# mcu.net
KiCad netlist of a schematic drawn in Altium Designer
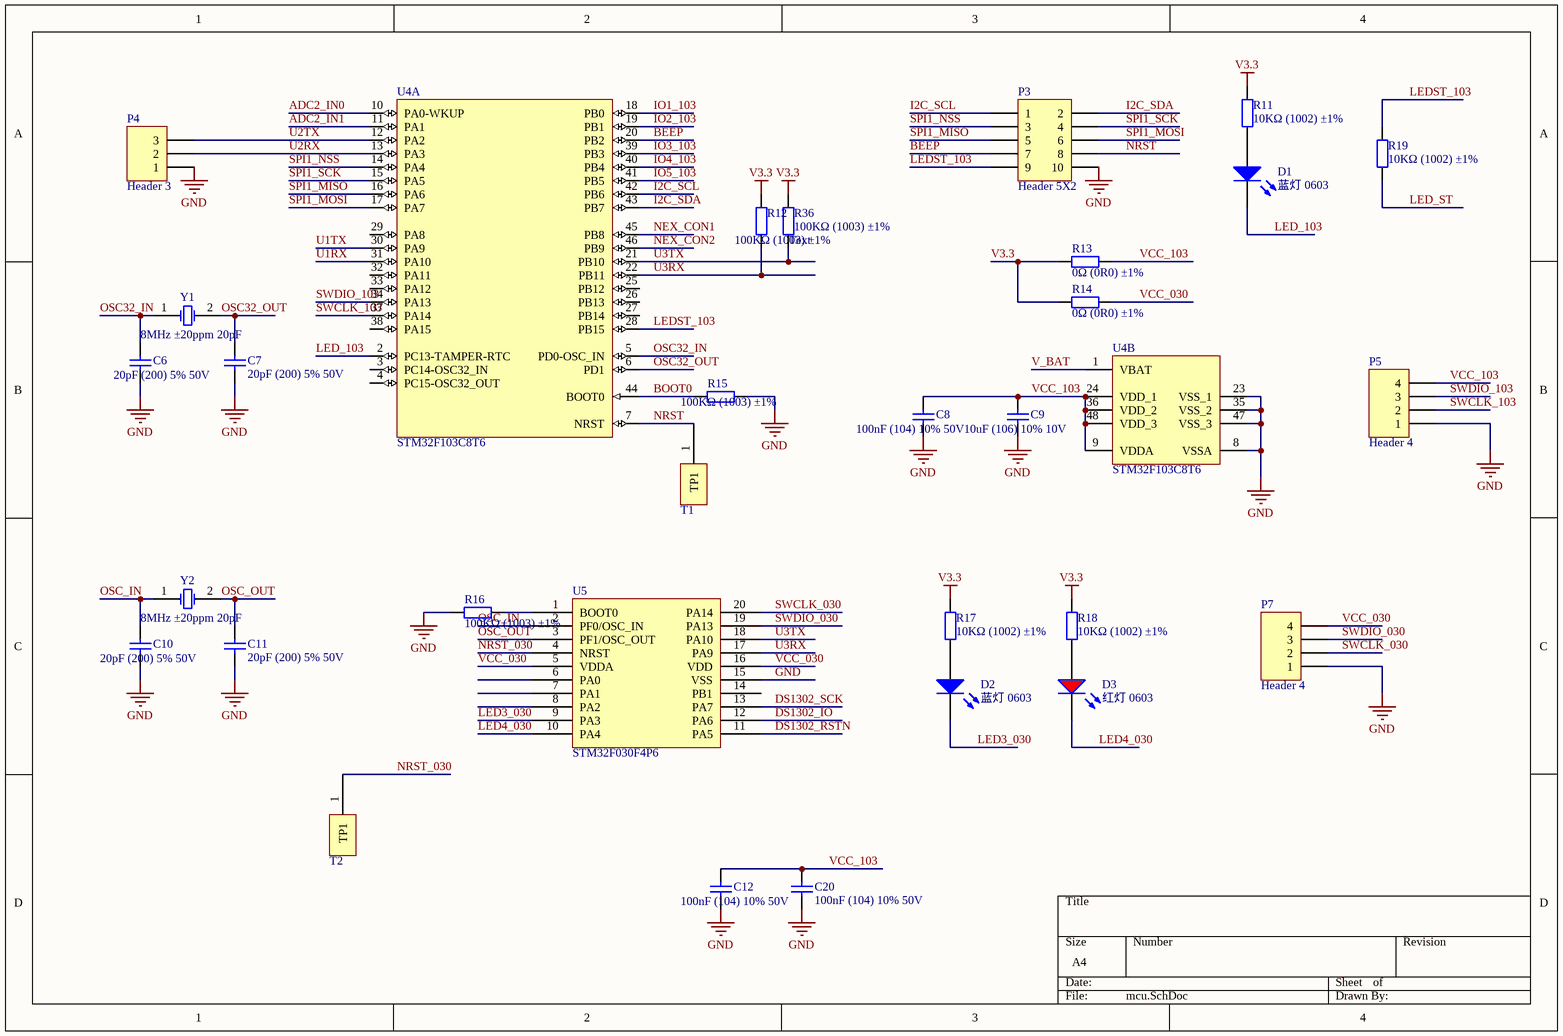
[diagram p0: mcu.SchDoc]

(export (version "E")
  (design (tool "Eeschema 10.0.6"))
  (components
    (comp (ref "C6")
      (value "20pF (200) 5% 50V")
      (footprint "0603_C")
      (description "贴片电容")
      (libsource (lib "Miscellaneous Devices LC") (part "0603 20pF (200) 5% 50V"))
    )
    (comp (ref "C7")
      (value "20pF (200) 5% 50V")
      (footprint "0603_C")
      (description "贴片电容")
      (libsource (lib "Miscellaneous Devices LC") (part "0603 20pF (200) 5% 50V"))
    )
    (comp (ref "C8")
      (value "100nF (104) 10% 50V")
      (footprint "0603_C")
      (description "贴片电容")
      (libsource (lib "Miscellaneous Devices LC") (part "0603 100nF (104) 10% 50V"))
    )
    (comp (ref "C9")
      (value "10uF (106) 10% 10V")
      (footprint "0603_C")
      (description "贴片电容")
      (libsource (lib "Miscellaneous Devices LC") (part "0603 10uF (106) 10% 10V"))
    )
    (comp (ref "C10")
      (value "20pF (200) 5% 50V")
      (footprint "0603_C")
      (description "贴片电容")
      (libsource (lib "Miscellaneous Devices LC") (part "0603 20pF (200) 5% 50V"))
    )
    (comp (ref "C11")
      (value "20pF (200) 5% 50V")
      (footprint "0603_C")
      (description "贴片电容")
      (libsource (lib "Miscellaneous Devices LC") (part "0603 20pF (200) 5% 50V"))
    )
    (comp (ref "C12")
      (value "100nF (104) 10% 50V")
      (footprint "1206_C")
      (description "贴片电容")
      (libsource (lib "Miscellaneous Devices LC") (part "1206 100nF (104) 10% 50V"))
    )
    (comp (ref "C20")
      (value "100nF (104) 10% 50V")
      (footprint "1206_C")
      (description "贴片电容")
      (libsource (lib "Miscellaneous Devices LC") (part "1206 100nF (104) 10% 50V"))
    )
    (comp (ref "D1")
      (value "蓝灯 0603")
      (footprint "0603_LED_S1")
      (description "发光二极管")
      (libsource (lib "Miscellaneous Devices LC") (part "0603 蓝灯"))
    )
    (comp (ref "D2")
      (value "蓝灯 0603")
      (footprint "0603_LED_S1")
      (description "发光二极管")
      (libsource (lib "Miscellaneous Devices LC") (part "0603 蓝灯"))
    )
    (comp (ref "D3")
      (value "红灯 0603")
      (footprint "0603_LED_S1")
      (description "发光二极管")
      (libsource (lib "Miscellaneous Devices LC") (part "0603 红灯"))
    )
    (comp (ref "P3")
      (value "Header 5X2")
      (footprint "HDR2X5")
      (description "Header, 5-Pin, Dual row")
      (fields (field (name "PUBLISHER") "Altium Limited"))
      (libsource (lib "Miscellaneous Connectors") (part "Header 5X2"))
    )
    (comp (ref "P4")
      (value "Header 3")
      (footprint "HDR1X3")
      (description "Header, 3-Pin")
      (fields (field (name "PUBLISHER") "Altium Limited"))
      (libsource (lib "Miscellaneous Connectors") (part "Header 3"))
    )
    (comp (ref "P5")
      (value "Header 4")
      (footprint "HDR1X4")
      (description "Header, 4-Pin")
      (fields (field (name "PUBLISHER") "Altium Limited"))
      (libsource (lib "Miscellaneous Connectors") (part "Header 4"))
    )
    (comp (ref "P7")
      (value "Header 4")
      (footprint "HDR1X4")
      (description "Header, 4-Pin")
      (fields (field (name "PUBLISHER") "Altium Limited"))
      (libsource (lib "Miscellaneous Connectors") (part "Header 4"))
    )
    (comp (ref "R11")
      (value "10KΩ (1002) ±1%")
      (footprint "0603_R")
      (description "贴片电阻")
      (libsource (lib "Miscellaneous Devices LC") (part "0603 10KΩ (1002) 1%"))
    )
    (comp (ref "R12")
      (value "100KΩ (1003) ±1%")
      (footprint "0603_R")
      (description "贴片电阻")
      (libsource (lib "Miscellaneous Devices LC") (part "0603 100KΩ (1003) 1%"))
    )
    (comp (ref "R13")
      (value "0Ω (0R0) ±1%")
      (footprint "1206_R")
      (description "贴片电阻")
      (libsource (lib "Miscellaneous Devices LC") (part "1206 0Ω (0R0) 1%"))
    )
    (comp (ref "R14")
      (value "0Ω (0R0) ±1%")
      (footprint "1206_R")
      (description "贴片电阻")
      (libsource (lib "Miscellaneous Devices LC") (part "1206 0Ω (0R0) 1%"))
    )
    (comp (ref "R15")
      (value "100KΩ (1003) ±1%")
      (footprint "0603_R")
      (description "贴片电阻")
      (libsource (lib "") (part "0603 100KΩ (1003) 1%_1"))
    )
    (comp (ref "R16")
      (value "100KΩ (1003) ±1%")
      (footprint "0603_R")
      (description "贴片电阻")
      (libsource (lib "") (part "0603 100KΩ (1003) 1%_1"))
    )
    (comp (ref "R17")
      (value "10KΩ (1002) ±1%")
      (footprint "0603_R")
      (description "贴片电阻")
      (libsource (lib "Miscellaneous Devices LC") (part "0603 10KΩ (1002) 1%"))
    )
    (comp (ref "R18")
      (value "10KΩ (1002) ±1%")
      (footprint "0603_R")
      (description "贴片电阻")
      (libsource (lib "Miscellaneous Devices LC") (part "0603 10KΩ (1002) 1%"))
    )
    (comp (ref "R19")
      (value "10KΩ (1002) ±1%")
      (footprint "0603_R")
      (description "贴片电阻")
      (libsource (lib "Miscellaneous Devices LC") (part "0603 10KΩ (1002) 1%"))
    )
    (comp (ref "R36")
      (value "100KΩ (1003) ±1%")
      (footprint "0603_R")
      (description "贴片电阻")
      (libsource (lib "Miscellaneous Devices LC") (part "0603 100KΩ (1003) 1%"))
    )
    (comp (ref "T1") (value "TP1") (footprint "TP1") (libsource (lib "CHK-I") (part "TP1")))
    (comp (ref "T2") (value "TP1") (footprint "TP1") (libsource (lib "CHK-I") (part "TP1")))
    (comp (ref "U4")
      (value "STM32F103C8T6")
      (footprint "LQFP-48_7x7x05P")
      (description "ARM")
      (libsource (lib "Miscellaneous Devices LC") (part "STM32F103C8T6"))
    )
    (comp (ref "U5")
      (value "STM32F030F4P6")
      (footprint "TSSOP-20")
      (description "ARM")
      (libsource (lib "Miscellaneous Devices LC") (part "STM32F030F4P6"))
    )
    (comp (ref "Y1")
      (value "8MHz ±20ppm 20pF")
      (footprint "SMD-5032_2P")
      (description "贴片晶振")
      (libsource (lib "Miscellaneous Devices LC") (part "SMD-5032_2P 8MHz 20ppm 20pF"))
    )
    (comp (ref "Y2")
      (value "8MHz ±20ppm 20pF")
      (footprint "SMD-5032_2P")
      (description "贴片晶振")
      (libsource (lib "Miscellaneous Devices LC") (part "SMD-5032_2P 8MHz 20ppm 20pF"))
    )
  )
  (nets
    (net (code "1") (name "/ADC2_IN0") (class "Default")
      (node (ref "U4") (pin "10") (pinfunction "PA0-WKUP_10") (pintype "bidirectional"))
    )
    (net (code "2") (name "/ADC2_IN1") (class "Default")
      (node (ref "U4") (pin "11") (pinfunction "PA1_11") (pintype "bidirectional"))
    )
    (net (code "3") (name "/BEEP") (class "Default")
      (node (ref "P3") (pin "7") (pinfunction "7_7") (pintype "passive"))
      (node (ref "U4") (pin "20") (pinfunction "PB2_20") (pintype "bidirectional"))
    )
    (net (code "4") (name "/BOOT0") (class "Default")
      (node (ref "R15") (pin "1") (pinfunction "1_1") (pintype "passive"))
      (node (ref "U4") (pin "44") (pinfunction "BOOT0_44") (pintype "input"))
    )
    (net (code "5") (name "/DS1302_IO") (class "Default")
      (node (ref "U5") (pin "12") (pinfunction "PA6_12") (pintype "passive"))
    )
    (net (code "6") (name "/DS1302_RSTN") (class "Default")
      (node (ref "U5") (pin "11") (pinfunction "PA5_11") (pintype "passive"))
    )
    (net (code "7") (name "/DS1302_SCK") (class "Default")
      (node (ref "U5") (pin "13") (pinfunction "PA7_13") (pintype "passive"))
    )
    (net (code "8") (name "/I2C_SCL") (class "Default")
      (node (ref "P3") (pin "1") (pinfunction "1_1") (pintype "passive"))
      (node (ref "U4") (pin "42") (pinfunction "PB6_42") (pintype "bidirectional"))
    )
    (net (code "9") (name "/I2C_SDA") (class "Default")
      (node (ref "P3") (pin "2") (pinfunction "2_2") (pintype "passive"))
      (node (ref "U4") (pin "43") (pinfunction "PB7_43") (pintype "bidirectional"))
    )
    (net (code "10") (name "/IO1_103") (class "Default")
      (node (ref "U4") (pin "18") (pinfunction "PB0_18") (pintype "bidirectional"))
    )
    (net (code "11") (name "/IO2_103") (class "Default")
      (node (ref "U4") (pin "19") (pinfunction "PB1_19") (pintype "bidirectional"))
    )
    (net (code "12") (name "/IO3_103") (class "Default")
      (node (ref "U4") (pin "39") (pinfunction "PB3_39") (pintype "bidirectional"))
    )
    (net (code "13") (name "/IO4_103") (class "Default")
      (node (ref "U4") (pin "40") (pinfunction "PB4_40") (pintype "bidirectional"))
    )
    (net (code "14") (name "/IO5_103") (class "Default")
      (node (ref "U4") (pin "41") (pinfunction "PB5_41") (pintype "bidirectional"))
    )
    (net (code "15") (name "/LED3_030") (class "Default")
      (node (ref "D2") (pin "K") (pinfunction "K_K") (pintype "passive"))
      (node (ref "U5") (pin "9") (pinfunction "PA3_9") (pintype "passive"))
    )
    (net (code "16") (name "/LED4_030") (class "Default")
      (node (ref "D3") (pin "K") (pinfunction "K_K") (pintype "passive"))
      (node (ref "U5") (pin "10") (pinfunction "PA4_10") (pintype "passive"))
    )
    (net (code "17") (name "/LEDST_103") (class "Default")
      (node (ref "P3") (pin "9") (pinfunction "9_9") (pintype "passive"))
      (node (ref "R19") (pin "2") (pinfunction "2_2") (pintype "passive"))
      (node (ref "U4") (pin "28") (pinfunction "PB15_28") (pintype "bidirectional"))
    )
    (net (code "18") (name "/LED_103") (class "Default")
      (node (ref "D1") (pin "K") (pinfunction "K_K") (pintype "passive"))
      (node (ref "U4") (pin "2") (pinfunction "PC13-TAMPER-RTC_2") (pintype "bidirectional"))
    )
    (net (code "19") (name "/LED_ST") (class "Default")
      (node (ref "R19") (pin "1") (pinfunction "1_1") (pintype "passive"))
    )
    (net (code "20") (name "/NEX_CON1") (class "Default")
      (node (ref "U4") (pin "45") (pinfunction "PB8_45") (pintype "bidirectional"))
    )
    (net (code "21") (name "/NEX_CON2") (class "Default")
      (node (ref "U4") (pin "46") (pinfunction "PB9_46") (pintype "bidirectional"))
    )
    (net (code "22") (name "/NRST") (class "Default")
      (node (ref "P3") (pin "8") (pinfunction "8_8") (pintype "passive"))
      (node (ref "T1") (pin "1") (pinfunction "TP1_1") (pintype "passive"))
      (node (ref "U4") (pin "7") (pinfunction "NRST_7") (pintype "bidirectional"))
    )
    (net (code "23") (name "/NRST_030") (class "Default")
      (node (ref "T2") (pin "1") (pinfunction "TP1_1") (pintype "passive"))
      (node (ref "U5") (pin "4") (pinfunction "NRST_4") (pintype "passive"))
    )
    (net (code "24") (name "/OSC32_IN") (class "Default")
      (node (ref "C6") (pin "2") (pinfunction "2_2") (pintype "passive"))
      (node (ref "U4") (pin "5") (pinfunction "PD0-OSC_IN_5") (pintype "bidirectional"))
      (node (ref "Y1") (pin "1") (pinfunction "OSC1_1") (pintype "passive"))
    )
    (net (code "25") (name "/OSC32_OUT") (class "Default")
      (node (ref "C7") (pin "2") (pinfunction "2_2") (pintype "passive"))
      (node (ref "U4") (pin "6") (pinfunction "PD1_6") (pintype "bidirectional"))
      (node (ref "Y1") (pin "2") (pinfunction "OSC2_2") (pintype "passive"))
    )
    (net (code "26") (name "/OSC_IN") (class "Default")
      (node (ref "C10") (pin "2") (pinfunction "2_2") (pintype "passive"))
      (node (ref "U5") (pin "2") (pinfunction "PF0/OSC_IN_2") (pintype "passive"))
      (node (ref "Y2") (pin "1") (pinfunction "OSC1_1") (pintype "passive"))
    )
    (net (code "27") (name "/OSC_OUT") (class "Default")
      (node (ref "C11") (pin "2") (pinfunction "2_2") (pintype "passive"))
      (node (ref "U5") (pin "3") (pinfunction "PF1/OSC_OUT_3") (pintype "passive"))
      (node (ref "Y2") (pin "2") (pinfunction "OSC2_2") (pintype "passive"))
    )
    (net (code "28") (name "/SPI1_MISO") (class "Default")
      (node (ref "P3") (pin "5") (pinfunction "5_5") (pintype "passive"))
      (node (ref "U4") (pin "16") (pinfunction "PA6_16") (pintype "bidirectional"))
    )
    (net (code "29") (name "/SPI1_MOSI") (class "Default")
      (node (ref "P3") (pin "6") (pinfunction "6_6") (pintype "passive"))
      (node (ref "U4") (pin "17") (pinfunction "PA7_17") (pintype "bidirectional"))
    )
    (net (code "30") (name "/SPI1_NSS") (class "Default")
      (node (ref "P3") (pin "3") (pinfunction "3_3") (pintype "passive"))
      (node (ref "U4") (pin "14") (pinfunction "PA4_14") (pintype "bidirectional"))
    )
    (net (code "31") (name "/SPI1_SCK") (class "Default")
      (node (ref "P3") (pin "4") (pinfunction "4_4") (pintype "passive"))
      (node (ref "U4") (pin "15") (pinfunction "PA5_15") (pintype "bidirectional"))
    )
    (net (code "32") (name "/SWCLK_030") (class "Default")
      (node (ref "P7") (pin "2") (pinfunction "2_2") (pintype "passive"))
      (node (ref "U5") (pin "20") (pinfunction "PA14_20") (pintype "passive"))
    )
    (net (code "33") (name "/SWCLK_103") (class "Default")
      (node (ref "P5") (pin "2") (pinfunction "2_2") (pintype "passive"))
      (node (ref "U4") (pin "37") (pinfunction "PA14_37") (pintype "bidirectional"))
    )
    (net (code "34") (name "/SWDIO_030") (class "Default")
      (node (ref "P7") (pin "3") (pinfunction "3_3") (pintype "passive"))
      (node (ref "U5") (pin "19") (pinfunction "PA13_19") (pintype "passive"))
    )
    (net (code "35") (name "/SWDIO_103") (class "Default")
      (node (ref "P5") (pin "3") (pinfunction "3_3") (pintype "passive"))
      (node (ref "U4") (pin "34") (pinfunction "PA13_34") (pintype "bidirectional"))
    )
    (net (code "36") (name "/U1RX") (class "Default")
      (node (ref "U4") (pin "31") (pinfunction "PA10_31") (pintype "bidirectional"))
    )
    (net (code "37") (name "/U1TX") (class "Default")
      (node (ref "U4") (pin "30") (pinfunction "PA9_30") (pintype "bidirectional"))
    )
    (net (code "38") (name "/U2RX") (class "Default")
      (node (ref "P4") (pin "2") (pinfunction "2_2") (pintype "passive"))
      (node (ref "U4") (pin "13") (pinfunction "PA3_13") (pintype "bidirectional"))
    )
    (net (code "39") (name "/U2TX") (class "Default")
      (node (ref "P4") (pin "3") (pinfunction "3_3") (pintype "passive"))
      (node (ref "U4") (pin "12") (pinfunction "PA2_12") (pintype "bidirectional"))
    )
    (net (code "40") (name "/U3RX") (class "Default")
      (node (ref "R12") (pin "1") (pinfunction "1_1") (pintype "passive"))
      (node (ref "U4") (pin "22") (pinfunction "PB11_22") (pintype "bidirectional"))
      (node (ref "U5") (pin "17") (pinfunction "PA9_17") (pintype "passive"))
    )
    (net (code "41") (name "/U3TX") (class "Default")
      (node (ref "R36") (pin "1") (pinfunction "1_1") (pintype "passive"))
      (node (ref "U4") (pin "21") (pinfunction "PB10_21") (pintype "bidirectional"))
      (node (ref "U5") (pin "18") (pinfunction "PA10_18") (pintype "passive"))
    )
    (net (code "42") (name "/VCC_030") (class "Default")
      (node (ref "P7") (pin "4") (pinfunction "4_4") (pintype "passive"))
      (node (ref "R14") (pin "2") (pinfunction "2_2") (pintype "passive"))
      (node (ref "U5") (pin "16") (pinfunction "VDD_16") (pintype "passive"))
      (node (ref "U5") (pin "5") (pinfunction "VDDA_5") (pintype "passive"))
    )
    (net (code "43") (name "/VCC_103") (class "Default")
      (node (ref "C12") (pin "2") (pinfunction "2_2") (pintype "passive"))
      (node (ref "C20") (pin "2") (pinfunction "2_2") (pintype "passive"))
      (node (ref "C8") (pin "2") (pinfunction "2_2") (pintype "passive"))
      (node (ref "C9") (pin "1") (pinfunction "1_1") (pintype "passive"))
      (node (ref "P5") (pin "4") (pinfunction "4_4") (pintype "passive"))
      (node (ref "R13") (pin "2") (pinfunction "2_2") (pintype "passive"))
      (node (ref "U4") (pin "24") (pinfunction "VDD_1_24") (pintype "power_in"))
      (node (ref "U4") (pin "36") (pinfunction "VDD_2_36") (pintype "power_in"))
      (node (ref "U4") (pin "48") (pinfunction "VDD_3_48") (pintype "power_in"))
      (node (ref "U4") (pin "9") (pinfunction "VDDA_9") (pintype "power_in"))
    )
    (net (code "44") (name "/V_BAT") (class "Default")
      (node (ref "U4") (pin "1") (pinfunction "VBAT_1") (pintype "power_in"))
    )
    (net (code "45") (name "GND") (class "Default")
      (node (ref "C10") (pin "1") (pinfunction "1_1") (pintype "passive"))
      (node (ref "C11") (pin "1") (pinfunction "1_1") (pintype "passive"))
      (node (ref "C12") (pin "1") (pinfunction "1_1") (pintype "passive"))
      (node (ref "C20") (pin "1") (pinfunction "1_1") (pintype "passive"))
      (node (ref "C6") (pin "1") (pinfunction "1_1") (pintype "passive"))
      (node (ref "C7") (pin "1") (pinfunction "1_1") (pintype "passive"))
      (node (ref "C8") (pin "1") (pinfunction "1_1") (pintype "passive"))
      (node (ref "C9") (pin "2") (pinfunction "2_2") (pintype "passive"))
      (node (ref "P3") (pin "10") (pinfunction "10_10") (pintype "passive"))
      (node (ref "P4") (pin "1") (pinfunction "1_1") (pintype "passive"))
      (node (ref "P5") (pin "1") (pinfunction "1_1") (pintype "passive"))
      (node (ref "P7") (pin "1") (pinfunction "1_1") (pintype "passive"))
      (node (ref "R15") (pin "2") (pinfunction "2_2") (pintype "passive"))
      (node (ref "R16") (pin "1") (pinfunction "1_1") (pintype "passive"))
      (node (ref "U4") (pin "23") (pinfunction "VSS_1_23") (pintype "power_in"))
      (node (ref "U4") (pin "35") (pinfunction "VSS_2_35") (pintype "power_in"))
      (node (ref "U4") (pin "47") (pinfunction "VSS_3_47") (pintype "power_in"))
      (node (ref "U4") (pin "8") (pinfunction "VSSA_8") (pintype "power_in"))
      (node (ref "U5") (pin "15") (pinfunction "VSS_15") (pintype "passive"))
    )
    (net (code "46") (name "Net-(D1-PadA)") (class "Default")
      (node (ref "D1") (pin "A") (pinfunction "A_A") (pintype "passive"))
      (node (ref "R11") (pin "1") (pinfunction "1_1") (pintype "passive"))
    )
    (net (code "47") (name "Net-(D2-PadA)") (class "Default")
      (node (ref "D2") (pin "A") (pinfunction "A_A") (pintype "passive"))
      (node (ref "R17") (pin "1") (pinfunction "1_1") (pintype "passive"))
    )
    (net (code "48") (name "Net-(D3-PadA)") (class "Default")
      (node (ref "D3") (pin "A") (pinfunction "A_A") (pintype "passive"))
      (node (ref "R18") (pin "1") (pinfunction "1_1") (pintype "passive"))
    )
    (net (code "49") (name "Net-(U5-BOOT0)") (class "Default")
      (node (ref "R16") (pin "2") (pinfunction "2_2") (pintype "passive"))
      (node (ref "U5") (pin "1") (pinfunction "BOOT0_1") (pintype "passive"))
    )
    (net (code "50") (name "V3.3") (class "Default")
      (node (ref "R11") (pin "2") (pinfunction "2_2") (pintype "passive"))
      (node (ref "R12") (pin "2") (pinfunction "2_2") (pintype "passive"))
      (node (ref "R13") (pin "1") (pinfunction "1_1") (pintype "passive"))
      (node (ref "R14") (pin "1") (pinfunction "1_1") (pintype "passive"))
      (node (ref "R17") (pin "2") (pinfunction "2_2") (pintype "passive"))
      (node (ref "R18") (pin "2") (pinfunction "2_2") (pintype "passive"))
      (node (ref "R36") (pin "2") (pinfunction "2_2") (pintype "passive"))
    )
    (net (code "51") (name "unconnected-(U4A-PA8-Pad29)") (class "Default")
      (node (ref "U4") (pin "29") (pinfunction "PA8_29") (pintype "bidirectional"))
    )
    (net (code "52") (name "unconnected-(U4A-PA11-Pad32)") (class "Default")
      (node (ref "U4") (pin "32") (pinfunction "PA11_32") (pintype "bidirectional"))
    )
    (net (code "53") (name "unconnected-(U4A-PA12-Pad33)") (class "Default")
      (node (ref "U4") (pin "33") (pinfunction "PA12_33") (pintype "bidirectional"))
    )
    (net (code "54") (name "unconnected-(U4A-PA15-Pad38)") (class "Default")
      (node (ref "U4") (pin "38") (pinfunction "PA15_38") (pintype "bidirectional"))
    )
    (net (code "55") (name "unconnected-(U4A-PB12-Pad25)") (class "Default")
      (node (ref "U4") (pin "25") (pinfunction "PB12_25") (pintype "bidirectional"))
    )
    (net (code "56") (name "unconnected-(U4A-PB13-Pad26)") (class "Default")
      (node (ref "U4") (pin "26") (pinfunction "PB13_26") (pintype "bidirectional"))
    )
    (net (code "57") (name "unconnected-(U4A-PB14-Pad27)") (class "Default")
      (node (ref "U4") (pin "27") (pinfunction "PB14_27") (pintype "bidirectional"))
    )
    (net (code "58") (name "unconnected-(U4A-PC14-OSC32_IN-Pad3)") (class "Default")
      (node (ref "U4") (pin "3") (pinfunction "PC14-OSC32_IN_3") (pintype "bidirectional"))
    )
    (net (code "59") (name "unconnected-(U4A-PC15-OSC32_OUT-Pad4)") (class "Default")
      (node (ref "U4") (pin "4") (pinfunction "PC15-OSC32_OUT_4") (pintype "bidirectional"))
    )
    (net (code "60") (name "unconnected-(U5-PA0-Pad6)") (class "Default")
      (node (ref "U5") (pin "6") (pinfunction "PA0_6") (pintype "passive"))
    )
    (net (code "61") (name "unconnected-(U5-PA1-Pad7)") (class "Default")
      (node (ref "U5") (pin "7") (pinfunction "PA1_7") (pintype "passive"))
    )
    (net (code "62") (name "unconnected-(U5-PA2-Pad8)") (class "Default")
      (node (ref "U5") (pin "8") (pinfunction "PA2_8") (pintype "passive"))
    )
    (net (code "63") (name "unconnected-(U5-PB1-Pad14)") (class "Default")
      (node (ref "U5") (pin "14") (pinfunction "PB1_14") (pintype "passive"))
    )
  )
)
